# UBEC_V3.net
KiCad netlist of a schematic drawn in EAGLE
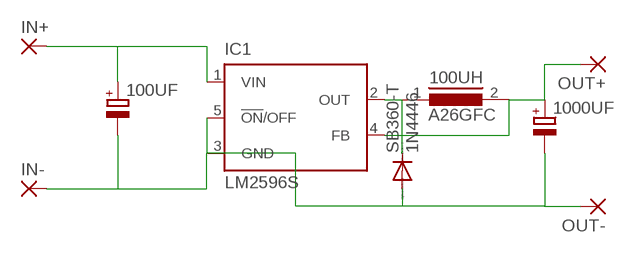
[diagram p0: schematic, sheet 1]

(export (version "E")
  (design (tool "Eeschema 10.0.6"))
  (components
    (comp (ref "100UF")
      (value "CPOL-EUE3.5-8")
      (footprint "eagle-import:E3,5-8")
      (libsource (lib "eagle-import") (part "CPOL-EUE3.5-8"))
    )
    (comp (ref "100UH")
      (value "A26GFC")
      (footprint "eagle-import:A26GFC")
      (libsource (lib "eagle-import") (part "A26GFC"))
    )
    (comp (ref "1000UF")
      (value "CPOL-EUE3.5-10")
      (footprint "eagle-import:E3,5-10")
      (libsource (lib "eagle-import") (part "CPOL-EUE3.5-10"))
    )
    (comp (ref "IC1")
      (value "LM2596S")
      (footprint "eagle-import:TO263-5")
      (fields (field (name "MF") "NATIONAL SEMICONDUCTOR") (field (name "MPN") "LM2596S-ADJ/NOPB"))
      (libsource (lib "eagle-import") (part "LM2596S"))
    )
    (comp (ref "IN+")
      (value "SMD5")
      (footprint "eagle-import:SMD2,54-5,08")
      (libsource (lib "eagle-import") (part "SMD5"))
    )
    (comp (ref "IN-")
      (value "SMD5")
      (footprint "eagle-import:SMD2,54-5,08")
      (libsource (lib "eagle-import") (part "SMD5"))
    )
    (comp (ref "OUT+")
      (value "SMD5")
      (footprint "eagle-import:SMD2,54-5,08")
      (libsource (lib "eagle-import") (part "SMD5"))
    )
    (comp (ref "OUT-")
      (value "SMD5")
      (footprint "eagle-import:SMD2,54-5,08")
      (libsource (lib "eagle-import") (part "SMD5"))
    )
    (comp (ref "SB360-T")
      (value "1N4446")
      (footprint "eagle-import:DO35-10")
      (libsource (lib "eagle-import") (part "1N4446"))
    )
  )
  (nets
    (net (code "1") (name "Net-(IC1-FB)") (class "Default")
      (node (ref "1000UF") (pin "+") (pinfunction "+_+") (pintype "passive"))
      (node (ref "100UH") (pin "2") (pinfunction "2_2") (pintype "passive"))
      (node (ref "IC1") (pin "4") (pinfunction "FB_4") (pintype "input"))
      (node (ref "OUT+") (pin "1") (pinfunction "P_1") (pintype "passive"))
    )
    (net (code "2") (name "Net-(IC1-GND)") (class "Default")
      (node (ref "1000UF") (pin "-") (pinfunction "-_-") (pintype "passive"))
      (node (ref "100UF") (pin "-") (pinfunction "-_-") (pintype "passive"))
      (node (ref "IC1") (pin "3") (pinfunction "GND_3") (pintype "power_in"))
      (node (ref "IC1") (pin "5") (pinfunction "~{ON}/OFF_5") (pintype "input"))
      (node (ref "IN-") (pin "1") (pinfunction "P_1") (pintype "passive"))
      (node (ref "OUT-") (pin "1") (pinfunction "P_1") (pintype "passive"))
      (node (ref "SB360-T") (pin "A") (pinfunction "A_A") (pintype "passive"))
    )
    (net (code "3") (name "Net-(IC1-OUT)") (class "Default")
      (node (ref "100UH") (pin "1") (pinfunction "1_1") (pintype "passive"))
      (node (ref "IC1") (pin "2") (pinfunction "OUT_2") (pintype "output"))
      (node (ref "SB360-T") (pin "C") (pinfunction "C_C") (pintype "passive"))
    )
    (net (code "4") (name "Net-(IC1-VIN)") (class "Default")
      (node (ref "100UF") (pin "+") (pinfunction "+_+") (pintype "passive"))
      (node (ref "IC1") (pin "1") (pinfunction "VIN_1") (pintype "input"))
      (node (ref "IN+") (pin "1") (pinfunction "P_1") (pintype "passive"))
    )
  )
)
